# mux-shield-pcb.net
KiCad netlist of a schematic drawn in EAGLE
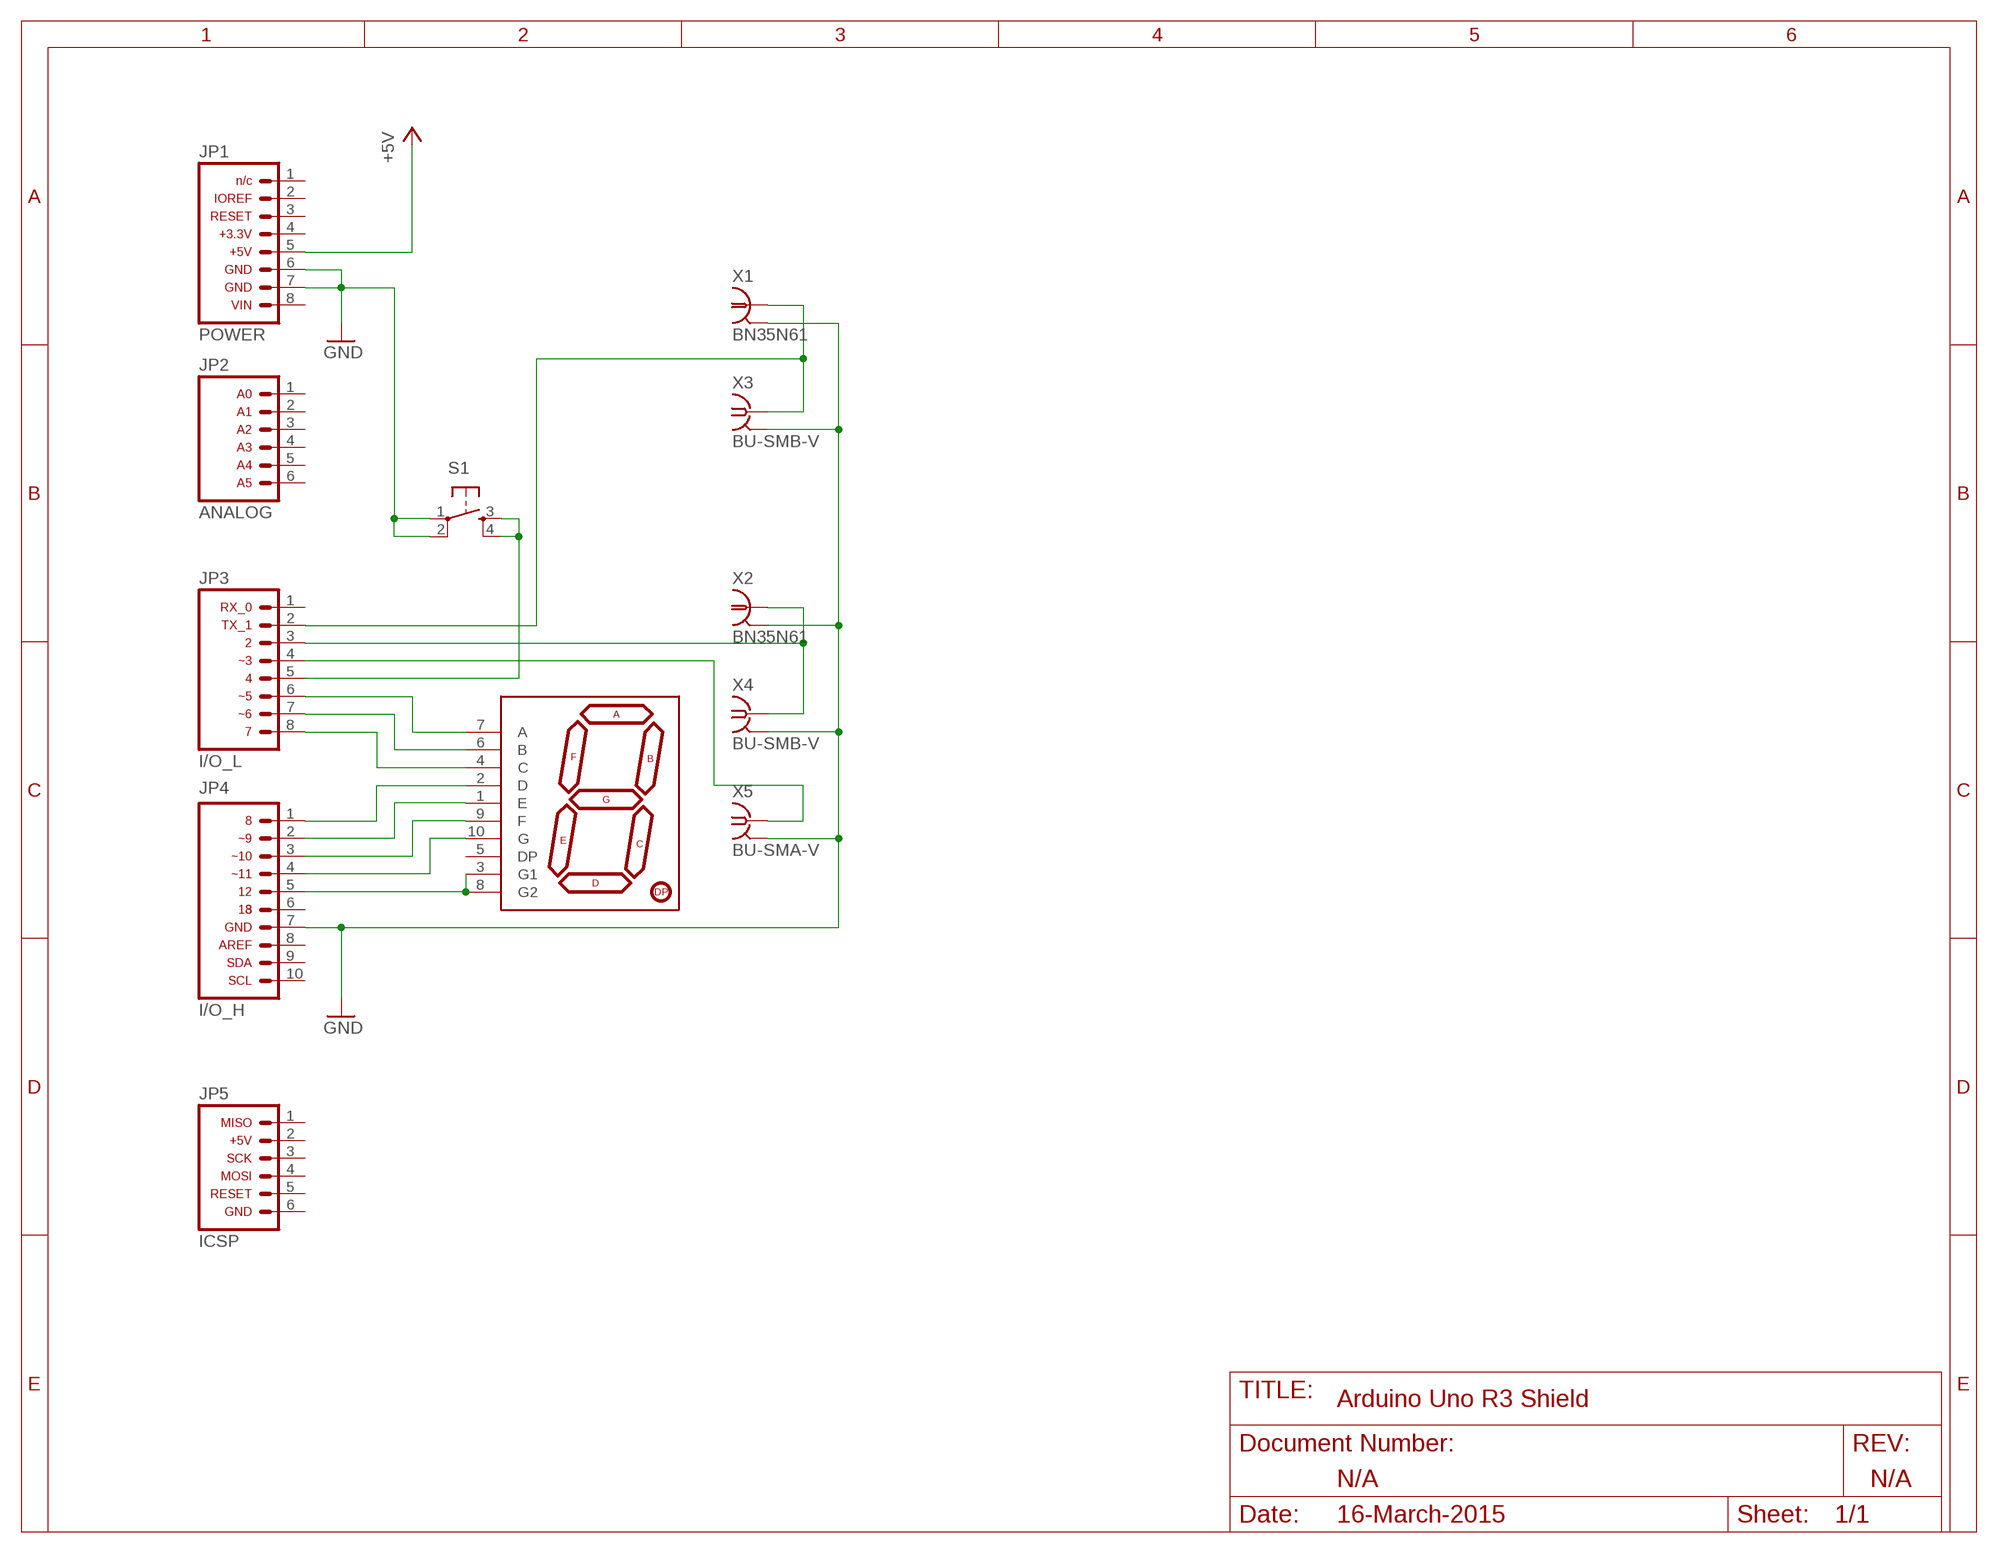
[diagram p0: schematic, sheet 1]

(export (version "E")
  (design (tool "Eeschema 10.0.6"))
  (components
    (comp (ref "JP1")
      (value "ARDUINO_CONN-POWERSIP")
      (footprint "eagle-import:CONN-1X08")
      (libsource (lib "eagle-import") (part "ARDUINO_CONN-POWERSIP"))
    )
    (comp (ref "JP2")
      (value "ARDUINO_CONN-ANALOGSIP")
      (footprint "eagle-import:CONN-1X06")
      (libsource (lib "eagle-import") (part "ARDUINO_CONN-ANALOGSIP"))
    )
    (comp (ref "JP3")
      (value "ARDUINO_CONN-IO_LSIP")
      (footprint "eagle-import:CONN-1X08")
      (libsource (lib "eagle-import") (part "ARDUINO_CONN-IO_LSIP"))
    )
    (comp (ref "JP4")
      (value "ARDUINO_CONN-IO_HSIP")
      (footprint "eagle-import:CONN-1X10")
      (libsource (lib "eagle-import") (part "ARDUINO_CONN-IO_HSIP"))
    )
    (comp (ref "JP5")
      (value "ARDUINO_CONN-ICSP")
      (footprint "eagle-import:CONN-2X03")
      (libsource (lib "eagle-import") (part "ARDUINO_CONN-ICSP"))
    )
    (comp (ref "S1")
      (value "TAC_SWITCHPTH")
      (footprint "eagle-import:TACTILE-PTH")
      (libsource (lib "eagle-import") (part "TAC_SWITCHPTH"))
    )
    (comp (ref "U$1")
      (value "7-SEGMENT-DISPLAY-1\"-RED")
      (footprint "eagle-import:7-SEGMENT-1_PTH")
      (libsource (lib "eagle-import") (part "7-SEGMENT-DISPLAY-1{dblquote}-RED"))
    )
    (comp (ref "X1")
      (value "BN35N61")
      (footprint "eagle-import:B35N61")
      (libsource (lib "eagle-import") (part "BN35N61"))
    )
    (comp (ref "X2")
      (value "BN35N61")
      (footprint "eagle-import:B35N61")
      (libsource (lib "eagle-import") (part "BN35N61"))
    )
    (comp (ref "X3")
      (value "BU-SMB-V")
      (footprint "eagle-import:BU-SMB-V")
      (libsource (lib "eagle-import") (part "BU-SMB-V"))
    )
    (comp (ref "X4")
      (value "BU-SMB-V")
      (footprint "eagle-import:BU-SMB-V")
      (libsource (lib "eagle-import") (part "BU-SMB-V"))
    )
    (comp (ref "X5")
      (value "BU-SMA-V")
      (footprint "eagle-import:BU-SMA-V")
      (libsource (lib "eagle-import") (part "BU-SMA-V"))
    )
  )
  (nets
    (net (code "1") (name "+5V") (class "Default")
      (node (ref "JP1") (pin "5") (pinfunction "5_5") (pintype "passive"))
    )
    (net (code "2") (name "GND") (class "Default")
      (node (ref "JP1") (pin "6") (pinfunction "6_6") (pintype "passive"))
      (node (ref "JP1") (pin "7") (pinfunction "7_7") (pintype "passive"))
      (node (ref "JP4") (pin "7") (pinfunction "7_7") (pintype "passive"))
      (node (ref "S1") (pin "1") (pinfunction "1_1") (pintype "passive"))
      (node (ref "S1") (pin "2") (pinfunction "2_2") (pintype "passive"))
      (node (ref "X1") (pin "2") (pinfunction "2_2") (pintype "passive"))
      (node (ref "X1") (pin "3") (pinfunction "2_3") (pintype "passive"))
      (node (ref "X1") (pin "4") (pinfunction "2_4") (pintype "passive"))
      (node (ref "X1") (pin "5") (pinfunction "2_5") (pintype "passive"))
      (node (ref "X2") (pin "2") (pinfunction "2_2") (pintype "passive"))
      (node (ref "X2") (pin "3") (pinfunction "2_3") (pintype "passive"))
      (node (ref "X2") (pin "4") (pinfunction "2_4") (pintype "passive"))
      (node (ref "X2") (pin "5") (pinfunction "2_5") (pintype "passive"))
      (node (ref "X3") (pin "2") (pinfunction "2_2") (pintype "passive"))
      (node (ref "X3") (pin "3") (pinfunction "2_3") (pintype "passive"))
      (node (ref "X3") (pin "4") (pinfunction "2_4") (pintype "passive"))
      (node (ref "X3") (pin "5") (pinfunction "2_5") (pintype "passive"))
      (node (ref "X4") (pin "2") (pinfunction "2_2") (pintype "passive"))
      (node (ref "X4") (pin "3") (pinfunction "2_3") (pintype "passive"))
      (node (ref "X4") (pin "4") (pinfunction "2_4") (pintype "passive"))
      (node (ref "X4") (pin "5") (pinfunction "2_5") (pintype "passive"))
      (node (ref "X5") (pin "2") (pinfunction "2_2") (pintype "passive"))
      (node (ref "X5") (pin "3") (pinfunction "2_3") (pintype "passive"))
      (node (ref "X5") (pin "4") (pinfunction "2_4") (pintype "passive"))
      (node (ref "X5") (pin "5") (pinfunction "2_5") (pintype "passive"))
    )
    (net (code "3") (name "Net-(JP3-Pad2)") (class "Default")
      (node (ref "JP3") (pin "2") (pinfunction "2_2") (pintype "passive"))
      (node (ref "X1") (pin "1") (pinfunction "1_1") (pintype "passive"))
      (node (ref "X3") (pin "1") (pinfunction "1_1") (pintype "passive"))
    )
    (net (code "4") (name "Net-(JP3-Pad3)") (class "Default")
      (node (ref "JP3") (pin "3") (pinfunction "3_3") (pintype "passive"))
      (node (ref "X2") (pin "1") (pinfunction "1_1") (pintype "passive"))
      (node (ref "X4") (pin "1") (pinfunction "1_1") (pintype "passive"))
    )
    (net (code "5") (name "Net-(JP3-Pad4)") (class "Default")
      (node (ref "JP3") (pin "4") (pinfunction "4_4") (pintype "passive"))
      (node (ref "X5") (pin "1") (pinfunction "1_1") (pintype "passive"))
    )
    (net (code "6") (name "Net-(JP3-Pad5)") (class "Default")
      (node (ref "JP3") (pin "5") (pinfunction "5_5") (pintype "passive"))
      (node (ref "S1") (pin "3") (pinfunction "3_3") (pintype "passive"))
      (node (ref "S1") (pin "4") (pinfunction "4_4") (pintype "passive"))
    )
    (net (code "7") (name "Net-(U$1-A)") (class "Default")
      (node (ref "JP3") (pin "6") (pinfunction "6_6") (pintype "passive"))
      (node (ref "U$1") (pin "7") (pinfunction "A_7") (pintype "bidirectional"))
    )
    (net (code "8") (name "Net-(U$1-B)") (class "Default")
      (node (ref "JP3") (pin "7") (pinfunction "7_7") (pintype "passive"))
      (node (ref "U$1") (pin "6") (pinfunction "B_6") (pintype "bidirectional"))
    )
    (net (code "9") (name "Net-(U$1-C)") (class "Default")
      (node (ref "JP3") (pin "8") (pinfunction "8_8") (pintype "passive"))
      (node (ref "U$1") (pin "4") (pinfunction "C_4") (pintype "bidirectional"))
    )
    (net (code "10") (name "Net-(U$1-D)") (class "Default")
      (node (ref "JP4") (pin "1") (pinfunction "1_1") (pintype "passive"))
      (node (ref "U$1") (pin "2") (pinfunction "D_2") (pintype "bidirectional"))
    )
    (net (code "11") (name "Net-(U$1-E)") (class "Default")
      (node (ref "JP4") (pin "2") (pinfunction "2_2") (pintype "passive"))
      (node (ref "U$1") (pin "1") (pinfunction "E_1") (pintype "bidirectional"))
    )
    (net (code "12") (name "Net-(U$1-F)") (class "Default")
      (node (ref "JP4") (pin "3") (pinfunction "3_3") (pintype "passive"))
      (node (ref "U$1") (pin "9") (pinfunction "F_9") (pintype "bidirectional"))
    )
    (net (code "13") (name "Net-(U$1-G)") (class "Default")
      (node (ref "JP4") (pin "4") (pinfunction "4_4") (pintype "passive"))
      (node (ref "U$1") (pin "10") (pinfunction "G_10") (pintype "bidirectional"))
    )
    (net (code "14") (name "Net-(U$1-G1)") (class "Default")
      (node (ref "JP4") (pin "5") (pinfunction "5_5") (pintype "passive"))
      (node (ref "U$1") (pin "3") (pinfunction "G1_3") (pintype "bidirectional"))
      (node (ref "U$1") (pin "8") (pinfunction "G2_8") (pintype "bidirectional"))
    )
    (net (code "15") (name "unconnected-(JP1-Pad1)") (class "Default")
      (node (ref "JP1") (pin "1") (pinfunction "1_1") (pintype "passive"))
    )
    (net (code "16") (name "unconnected-(JP1-Pad2)") (class "Default")
      (node (ref "JP1") (pin "2") (pinfunction "2_2") (pintype "passive"))
    )
    (net (code "17") (name "unconnected-(JP1-Pad3)") (class "Default")
      (node (ref "JP1") (pin "3") (pinfunction "3_3") (pintype "passive"))
    )
    (net (code "18") (name "unconnected-(JP1-Pad4)") (class "Default")
      (node (ref "JP1") (pin "4") (pinfunction "4_4") (pintype "passive"))
    )
    (net (code "19") (name "unconnected-(JP1-Pad8)") (class "Default")
      (node (ref "JP1") (pin "8") (pinfunction "8_8") (pintype "passive"))
    )
    (net (code "20") (name "unconnected-(JP2-Pad1)") (class "Default")
      (node (ref "JP2") (pin "1") (pinfunction "1_1") (pintype "passive"))
    )
    (net (code "21") (name "unconnected-(JP2-Pad2)") (class "Default")
      (node (ref "JP2") (pin "2") (pinfunction "2_2") (pintype "passive"))
    )
    (net (code "22") (name "unconnected-(JP2-Pad3)") (class "Default")
      (node (ref "JP2") (pin "3") (pinfunction "3_3") (pintype "passive"))
    )
    (net (code "23") (name "unconnected-(JP2-Pad4)") (class "Default")
      (node (ref "JP2") (pin "4") (pinfunction "4_4") (pintype "passive"))
    )
    (net (code "24") (name "unconnected-(JP2-Pad5)") (class "Default")
      (node (ref "JP2") (pin "5") (pinfunction "5_5") (pintype "passive"))
    )
    (net (code "25") (name "unconnected-(JP2-Pad6)") (class "Default")
      (node (ref "JP2") (pin "6") (pinfunction "6_6") (pintype "passive"))
    )
    (net (code "26") (name "unconnected-(JP3-Pad1)") (class "Default")
      (node (ref "JP3") (pin "1") (pinfunction "1_1") (pintype "passive"))
    )
    (net (code "27") (name "unconnected-(JP4-Pad6)") (class "Default")
      (node (ref "JP4") (pin "6") (pinfunction "6_6") (pintype "passive"))
    )
    (net (code "28") (name "unconnected-(JP4-Pad8)") (class "Default")
      (node (ref "JP4") (pin "8") (pinfunction "8_8") (pintype "passive"))
    )
    (net (code "29") (name "unconnected-(JP4-Pad9)") (class "Default")
      (node (ref "JP4") (pin "9") (pinfunction "9_9") (pintype "passive"))
    )
    (net (code "30") (name "unconnected-(JP4-Pad10)") (class "Default")
      (node (ref "JP4") (pin "10") (pinfunction "10_10") (pintype "passive"))
    )
    (net (code "31") (name "unconnected-(JP5-Pad1)") (class "Default")
      (node (ref "JP5") (pin "1") (pinfunction "1_1") (pintype "passive"))
    )
    (net (code "32") (name "unconnected-(JP5-Pad2)") (class "Default")
      (node (ref "JP5") (pin "2") (pinfunction "2_2") (pintype "passive"))
    )
    (net (code "33") (name "unconnected-(JP5-Pad3)") (class "Default")
      (node (ref "JP5") (pin "3") (pinfunction "3_3") (pintype "passive"))
    )
    (net (code "34") (name "unconnected-(JP5-Pad4)") (class "Default")
      (node (ref "JP5") (pin "4") (pinfunction "4_4") (pintype "passive"))
    )
    (net (code "35") (name "unconnected-(JP5-Pad5)") (class "Default")
      (node (ref "JP5") (pin "5") (pinfunction "5_5") (pintype "passive"))
    )
    (net (code "36") (name "unconnected-(JP5-Pad6)") (class "Default")
      (node (ref "JP5") (pin "6") (pinfunction "6_6") (pintype "passive"))
    )
    (net (code "37") (name "unconnected-(U$1-DP-Pad5)") (class "Default")
      (node (ref "U$1") (pin "5") (pinfunction "DP_5") (pintype "bidirectional"))
    )
  )
)
